# Adaptadores_Seriales.net
KiCad netlist of a schematic drawn in EAGLE
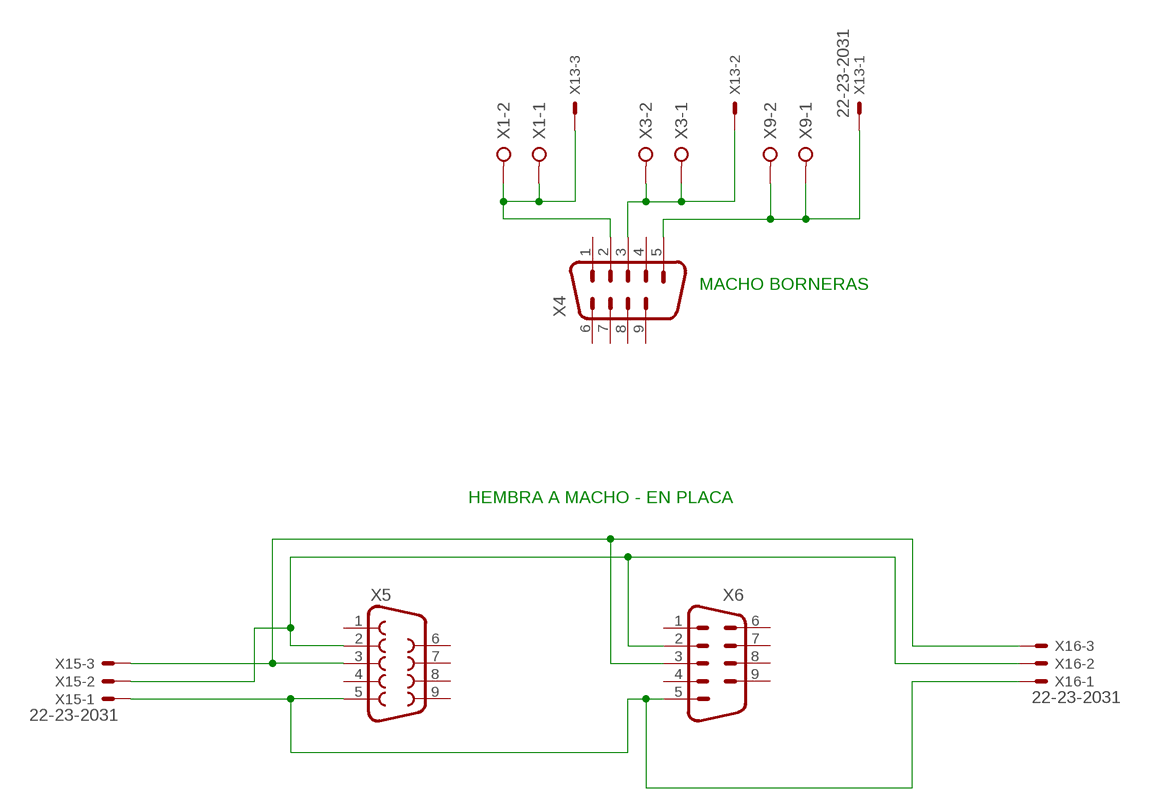
[diagram p0: schematic, sheet 1, part 1 of 2]
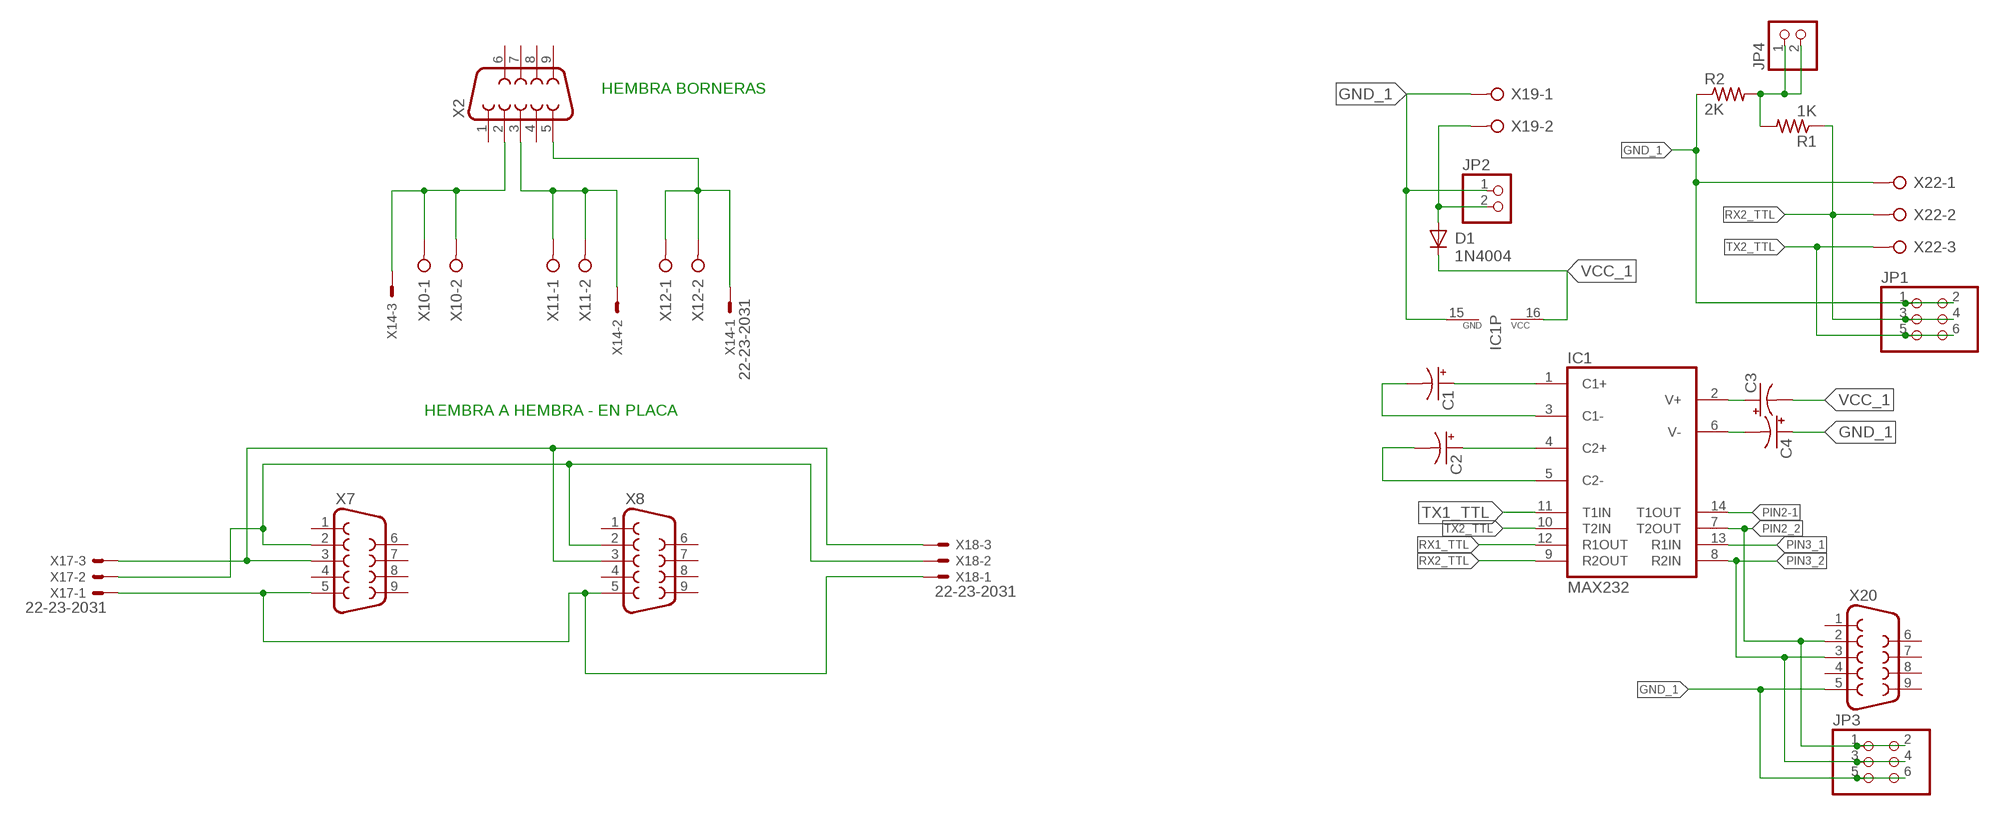
[diagram p1: schematic, sheet 1, part 2 of 2]

(export (version "E")
  (design (tool "Eeschema 10.0.6"))
  (components
    (comp (ref "C1")
      (value "10UF-25V-20%(PTH)KIT")
      (footprint "eagle-import:CPOL-RADIAL-10UF-25V-KIT")
      (libsource (lib "eagle-import") (part "10UF-25V-20%(PTH)KIT"))
    )
    (comp (ref "C2")
      (value "10UF-25V-20%(PTH)KIT")
      (footprint "eagle-import:CPOL-RADIAL-10UF-25V-KIT")
      (libsource (lib "eagle-import") (part "10UF-25V-20%(PTH)KIT"))
    )
    (comp (ref "C3")
      (value "10UF-25V-20%(PTH)KIT")
      (footprint "eagle-import:CPOL-RADIAL-10UF-25V-KIT")
      (libsource (lib "eagle-import") (part "10UF-25V-20%(PTH)KIT"))
    )
    (comp (ref "C4")
      (value "10UF-25V-20%(PTH)KIT")
      (footprint "eagle-import:CPOL-RADIAL-10UF-25V-KIT")
      (libsource (lib "eagle-import") (part "10UF-25V-20%(PTH)KIT"))
    )
    (comp (ref "D1")
      (value "1N4004")
      (footprint "eagle-import:DO41-10")
      (libsource (lib "eagle-import") (part "1N4004"))
    )
    (comp (ref "IC1")
      (value "MAX232")
      (footprint "eagle-import:DIL16")
      (fields (field (name "MF") "MAXIM") (field (name "MPN") "MAX232ACPE+"))
      (libsource (lib "eagle-import") (part "MAX232"))
    )
    (comp (ref "JP1")
      (value "PINHD-2X3")
      (footprint "eagle-import:2X03")
      (libsource (lib "eagle-import") (part "PINHD-2X3"))
    )
    (comp (ref "JP2")
      (value "PINHD-1X2")
      (footprint "eagle-import:1X02")
      (libsource (lib "eagle-import") (part "PINHD-1X2"))
    )
    (comp (ref "JP3")
      (value "PINHD-2X3")
      (footprint "eagle-import:2X03")
      (libsource (lib "eagle-import") (part "PINHD-2X3"))
    )
    (comp (ref "JP4")
      (value "PINHD-1X2")
      (footprint "eagle-import:1X02")
      (libsource (lib "eagle-import") (part "PINHD-1X2"))
    )
    (comp (ref "R1")
      (value "1K")
      (footprint "eagle-import:0204V")
      (libsource (lib "eagle-import") (part "R-US_0204/2V"))
    )
    (comp (ref "R2")
      (value "2K")
      (footprint "eagle-import:0204V")
      (libsource (lib "eagle-import") (part "R-US_0204/2V"))
    )
    (comp (ref "X1")
      (value "W237-02P")
      (footprint "eagle-import:W237-132")
      (libsource (lib "eagle-import") (part "W237-02P"))
    )
    (comp (ref "X2")
      (value "F09HP")
      (footprint "eagle-import:F09HP")
      (libsource (lib "eagle-import") (part "F09HP"))
    )
    (comp (ref "X3")
      (value "W237-02P")
      (footprint "eagle-import:W237-132")
      (libsource (lib "eagle-import") (part "W237-02P"))
    )
    (comp (ref "X4")
      (value "M09HP")
      (footprint "eagle-import:M09HP")
      (libsource (lib "eagle-import") (part "M09HP"))
    )
    (comp (ref "X5")
      (value "F09D")
      (footprint "eagle-import:F09D")
      (libsource (lib "eagle-import") (part "F09D"))
    )
    (comp (ref "X6")
      (value "M09D")
      (footprint "eagle-import:M09D")
      (libsource (lib "eagle-import") (part "M09D"))
    )
    (comp (ref "X7")
      (value "F09D")
      (footprint "eagle-import:F09D")
      (libsource (lib "eagle-import") (part "F09D"))
    )
    (comp (ref "X8")
      (value "F09D")
      (footprint "eagle-import:F09D")
      (libsource (lib "eagle-import") (part "F09D"))
    )
    (comp (ref "X9")
      (value "W237-02P")
      (footprint "eagle-import:W237-132")
      (libsource (lib "eagle-import") (part "W237-02P"))
    )
    (comp (ref "X10")
      (value "W237-02P")
      (footprint "eagle-import:W237-132")
      (libsource (lib "eagle-import") (part "W237-02P"))
    )
    (comp (ref "X11")
      (value "W237-02P")
      (footprint "eagle-import:W237-132")
      (libsource (lib "eagle-import") (part "W237-02P"))
    )
    (comp (ref "X12")
      (value "W237-02P")
      (footprint "eagle-import:W237-132")
      (libsource (lib "eagle-import") (part "W237-02P"))
    )
    (comp (ref "X13")
      (value "22-23-2031")
      (footprint "eagle-import:22-23-2031")
      (fields (field (name "MF") "MOLEX"))
      (libsource (lib "eagle-import") (part "22-23-2031"))
    )
    (comp (ref "X14")
      (value "22-23-2031")
      (footprint "eagle-import:22-23-2031")
      (fields (field (name "MF") "MOLEX"))
      (libsource (lib "eagle-import") (part "22-23-2031"))
    )
    (comp (ref "X15")
      (value "22-23-2031")
      (footprint "eagle-import:22-23-2031")
      (fields (field (name "MF") "MOLEX"))
      (libsource (lib "eagle-import") (part "22-23-2031"))
    )
    (comp (ref "X16")
      (value "22-23-2031")
      (footprint "eagle-import:22-23-2031")
      (fields (field (name "MF") "MOLEX"))
      (libsource (lib "eagle-import") (part "22-23-2031"))
    )
    (comp (ref "X17")
      (value "22-23-2031")
      (footprint "eagle-import:22-23-2031")
      (fields (field (name "MF") "MOLEX"))
      (libsource (lib "eagle-import") (part "22-23-2031"))
    )
    (comp (ref "X18")
      (value "22-23-2031")
      (footprint "eagle-import:22-23-2031")
      (fields (field (name "MF") "MOLEX"))
      (libsource (lib "eagle-import") (part "22-23-2031"))
    )
    (comp (ref "X19")
      (value "W237-02P")
      (footprint "eagle-import:W237-132")
      (fields (field (name "OC_FARNELL") "unknown") (field (name "OC_NEWARK") "unknown"))
      (libsource (lib "eagle-import") (part "W237-02P"))
    )
    (comp (ref "X20")
      (value "F09D")
      (footprint "eagle-import:F09D")
      (fields (field (name "OC_FARNELL") "unknown") (field (name "OC_NEWARK") "unknown"))
      (libsource (lib "eagle-import") (part "F09D"))
    )
    (comp (ref "X22")
      (value "W237-03P")
      (footprint "eagle-import:W237-133")
      (libsource (lib "eagle-import") (part "W237-03P"))
    )
  )
  (nets
    (net (code "1") (name "GND_1") (class "Default")
      (node (ref "C4") (pin "1") (pinfunction "+_1") (pintype "passive"))
      (node (ref "IC1") (pin "15") (pinfunction "GND_15") (pintype "power_in"))
      (node (ref "JP1") (pin "1") (pinfunction "1_1") (pintype "passive"))
      (node (ref "JP1") (pin "2") (pinfunction "2_2") (pintype "passive"))
      (node (ref "JP2") (pin "1") (pinfunction "1_1") (pintype "passive"))
      (node (ref "JP3") (pin "5") (pinfunction "5_5") (pintype "passive"))
      (node (ref "JP3") (pin "6") (pinfunction "6_6") (pintype "passive"))
      (node (ref "R2") (pin "1") (pinfunction "1_1") (pintype "passive"))
      (node (ref "X19") (pin "1") (pinfunction "KL_1") (pintype "passive"))
      (node (ref "X20") (pin "5") (pinfunction "5_5") (pintype "passive"))
      (node (ref "X22") (pin "1") (pinfunction "KL_1") (pintype "passive"))
    )
    (net (code "2") (name "Net-(C1-+)") (class "Default")
      (node (ref "C1") (pin "1") (pinfunction "+_1") (pintype "passive"))
      (node (ref "IC1") (pin "1") (pinfunction "C1+_1") (pintype "bidirectional"))
    )
    (net (code "3") (name "Net-(C1--)") (class "Default")
      (node (ref "C1") (pin "2") (pinfunction "-_2") (pintype "passive"))
      (node (ref "IC1") (pin "3") (pinfunction "C1-_3") (pintype "bidirectional"))
    )
    (net (code "4") (name "Net-(C2-+)") (class "Default")
      (node (ref "C2") (pin "1") (pinfunction "+_1") (pintype "passive"))
      (node (ref "IC1") (pin "4") (pinfunction "C2+_4") (pintype "bidirectional"))
    )
    (net (code "5") (name "Net-(C2--)") (class "Default")
      (node (ref "C2") (pin "2") (pinfunction "-_2") (pintype "passive"))
      (node (ref "IC1") (pin "5") (pinfunction "C2-_5") (pintype "bidirectional"))
    )
    (net (code "6") (name "Net-(C3-+)") (class "Default")
      (node (ref "C3") (pin "1") (pinfunction "+_1") (pintype "passive"))
      (node (ref "IC1") (pin "2") (pinfunction "V+_2") (pintype "bidirectional"))
    )
    (net (code "7") (name "Net-(C4--)") (class "Default")
      (node (ref "C4") (pin "2") (pinfunction "-_2") (pintype "passive"))
      (node (ref "IC1") (pin "6") (pinfunction "V-_6") (pintype "bidirectional"))
    )
    (net (code "8") (name "Net-(JP4-Pad1)") (class "Default")
      (node (ref "JP4") (pin "1") (pinfunction "1_1") (pintype "passive"))
      (node (ref "JP4") (pin "2") (pinfunction "2_2") (pintype "passive"))
      (node (ref "R1") (pin "2") (pinfunction "2_2") (pintype "passive"))
      (node (ref "R2") (pin "2") (pinfunction "2_2") (pintype "passive"))
    )
    (net (code "9") (name "Net-(X10A-KL)") (class "Default")
      (node (ref "X10") (pin "1") (pinfunction "KL_1") (pintype "passive"))
      (node (ref "X10") (pin "2") (pinfunction "KL_2") (pintype "passive"))
      (node (ref "X14") (pin "3") (pinfunction "S_3") (pintype "passive"))
      (node (ref "X2") (pin "2") (pinfunction "2_2") (pintype "passive"))
    )
    (net (code "10") (name "Net-(X11A-KL)") (class "Default")
      (node (ref "X11") (pin "1") (pinfunction "KL_1") (pintype "passive"))
      (node (ref "X11") (pin "2") (pinfunction "KL_2") (pintype "passive"))
      (node (ref "X14") (pin "2") (pinfunction "S_2") (pintype "passive"))
      (node (ref "X2") (pin "3") (pinfunction "3_3") (pintype "passive"))
    )
    (net (code "11") (name "Net-(X12A-KL)") (class "Default")
      (node (ref "X12") (pin "1") (pinfunction "KL_1") (pintype "passive"))
      (node (ref "X12") (pin "2") (pinfunction "KL_2") (pintype "passive"))
      (node (ref "X14") (pin "1") (pinfunction "S_1") (pintype "passive"))
      (node (ref "X2") (pin "5") (pinfunction "5_5") (pintype "passive"))
    )
    (net (code "12") (name "Net-(X13A-S)") (class "Default")
      (node (ref "X13") (pin "1") (pinfunction "S_1") (pintype "passive"))
      (node (ref "X4") (pin "5") (pinfunction "5_5") (pintype "passive"))
      (node (ref "X9") (pin "1") (pinfunction "KL_1") (pintype "passive"))
      (node (ref "X9") (pin "2") (pinfunction "KL_2") (pintype "passive"))
    )
    (net (code "13") (name "Net-(X13B-S)") (class "Default")
      (node (ref "X13") (pin "2") (pinfunction "S_2") (pintype "passive"))
      (node (ref "X3") (pin "1") (pinfunction "KL_1") (pintype "passive"))
      (node (ref "X3") (pin "2") (pinfunction "KL_2") (pintype "passive"))
      (node (ref "X4") (pin "3") (pinfunction "3_3") (pintype "passive"))
    )
    (net (code "14") (name "Net-(X13C-S)") (class "Default")
      (node (ref "X1") (pin "1") (pinfunction "KL_1") (pintype "passive"))
      (node (ref "X1") (pin "2") (pinfunction "KL_2") (pintype "passive"))
      (node (ref "X13") (pin "3") (pinfunction "S_3") (pintype "passive"))
      (node (ref "X4") (pin "2") (pinfunction "2_2") (pintype "passive"))
    )
    (net (code "15") (name "Net-(X15A-S)") (class "Default")
      (node (ref "X15") (pin "1") (pinfunction "S_1") (pintype "passive"))
      (node (ref "X16") (pin "1") (pinfunction "S_1") (pintype "passive"))
      (node (ref "X5") (pin "5") (pinfunction "5_5") (pintype "passive"))
      (node (ref "X6") (pin "5") (pinfunction "5_5") (pintype "passive"))
    )
    (net (code "16") (name "Net-(X15B-S)") (class "Default")
      (node (ref "X15") (pin "2") (pinfunction "S_2") (pintype "passive"))
      (node (ref "X16") (pin "2") (pinfunction "S_2") (pintype "passive"))
      (node (ref "X5") (pin "2") (pinfunction "2_2") (pintype "passive"))
      (node (ref "X6") (pin "2") (pinfunction "2_2") (pintype "passive"))
    )
    (net (code "17") (name "Net-(X15C-S)") (class "Default")
      (node (ref "X15") (pin "3") (pinfunction "S_3") (pintype "passive"))
      (node (ref "X16") (pin "3") (pinfunction "S_3") (pintype "passive"))
      (node (ref "X5") (pin "3") (pinfunction "3_3") (pintype "passive"))
      (node (ref "X6") (pin "3") (pinfunction "3_3") (pintype "passive"))
    )
    (net (code "18") (name "Net-(X17A-S)") (class "Default")
      (node (ref "X17") (pin "1") (pinfunction "S_1") (pintype "passive"))
      (node (ref "X18") (pin "1") (pinfunction "S_1") (pintype "passive"))
      (node (ref "X7") (pin "5") (pinfunction "5_5") (pintype "passive"))
      (node (ref "X8") (pin "5") (pinfunction "5_5") (pintype "passive"))
    )
    (net (code "19") (name "Net-(X17B-S)") (class "Default")
      (node (ref "X17") (pin "2") (pinfunction "S_2") (pintype "passive"))
      (node (ref "X18") (pin "2") (pinfunction "S_2") (pintype "passive"))
      (node (ref "X7") (pin "2") (pinfunction "2_2") (pintype "passive"))
      (node (ref "X8") (pin "2") (pinfunction "2_2") (pintype "passive"))
    )
    (net (code "20") (name "Net-(X17C-S)") (class "Default")
      (node (ref "X17") (pin "3") (pinfunction "S_3") (pintype "passive"))
      (node (ref "X18") (pin "3") (pinfunction "S_3") (pintype "passive"))
      (node (ref "X7") (pin "3") (pinfunction "3_3") (pintype "passive"))
      (node (ref "X8") (pin "3") (pinfunction "3_3") (pintype "passive"))
    )
    (net (code "21") (name "Net-(X19B-KL)") (class "Default")
      (node (ref "D1") (pin "A") (pinfunction "A_A") (pintype "passive"))
      (node (ref "JP2") (pin "2") (pinfunction "2_2") (pintype "passive"))
      (node (ref "X19") (pin "2") (pinfunction "KL_2") (pintype "passive"))
    )
    (net (code "22") (name "PIN2-1") (class "Default")
      (node (ref "IC1") (pin "14") (pinfunction "T1OUT_14") (pintype "output"))
    )
    (net (code "23") (name "PIN2_2") (class "Default")
      (node (ref "IC1") (pin "7") (pinfunction "T2OUT_7") (pintype "output"))
      (node (ref "JP3") (pin "1") (pinfunction "1_1") (pintype "passive"))
      (node (ref "JP3") (pin "2") (pinfunction "2_2") (pintype "passive"))
      (node (ref "X20") (pin "2") (pinfunction "2_2") (pintype "passive"))
    )
    (net (code "24") (name "PIN3_1") (class "Default")
      (node (ref "IC1") (pin "13") (pinfunction "R1IN_13") (pintype "input"))
    )
    (net (code "25") (name "PIN3_2") (class "Default")
      (node (ref "IC1") (pin "8") (pinfunction "R2IN_8") (pintype "input"))
      (node (ref "JP3") (pin "3") (pinfunction "3_3") (pintype "passive"))
      (node (ref "JP3") (pin "4") (pinfunction "4_4") (pintype "passive"))
      (node (ref "X20") (pin "3") (pinfunction "3_3") (pintype "passive"))
    )
    (net (code "26") (name "RX1_TTL") (class "Default")
      (node (ref "IC1") (pin "12") (pinfunction "R1OUT_12") (pintype "output"))
    )
    (net (code "27") (name "RX2_TTL") (class "Default")
      (node (ref "IC1") (pin "9") (pinfunction "R2OUT_9") (pintype "output"))
      (node (ref "JP1") (pin "3") (pinfunction "3_3") (pintype "passive"))
      (node (ref "JP1") (pin "4") (pinfunction "4_4") (pintype "passive"))
      (node (ref "R1") (pin "1") (pinfunction "1_1") (pintype "passive"))
      (node (ref "X22") (pin "2") (pinfunction "KL_2") (pintype "passive"))
    )
    (net (code "28") (name "TX1_TTL") (class "Default")
      (node (ref "IC1") (pin "11") (pinfunction "T1IN_11") (pintype "input"))
    )
    (net (code "29") (name "TX2_TTL") (class "Default")
      (node (ref "IC1") (pin "10") (pinfunction "T2IN_10") (pintype "input"))
      (node (ref "JP1") (pin "5") (pinfunction "5_5") (pintype "passive"))
      (node (ref "JP1") (pin "6") (pinfunction "6_6") (pintype "passive"))
      (node (ref "X22") (pin "3") (pinfunction "KL_3") (pintype "passive"))
    )
    (net (code "30") (name "VCC_1") (class "Default")
      (node (ref "C3") (pin "2") (pinfunction "-_2") (pintype "passive"))
      (node (ref "D1") (pin "C") (pinfunction "C_C") (pintype "passive"))
      (node (ref "IC1") (pin "16") (pinfunction "VCC_16") (pintype "power_in"))
    )
    (net (code "31") (name "unconnected-(X2-Pad1)") (class "Default")
      (node (ref "X2") (pin "1") (pinfunction "1_1") (pintype "passive"))
    )
    (net (code "32") (name "unconnected-(X2-Pad4)") (class "Default")
      (node (ref "X2") (pin "4") (pinfunction "4_4") (pintype "passive"))
    )
    (net (code "33") (name "unconnected-(X2-Pad6)") (class "Default")
      (node (ref "X2") (pin "6") (pinfunction "6_6") (pintype "passive"))
    )
    (net (code "34") (name "unconnected-(X2-Pad7)") (class "Default")
      (node (ref "X2") (pin "7") (pinfunction "7_7") (pintype "passive"))
    )
    (net (code "35") (name "unconnected-(X2-Pad8)") (class "Default")
      (node (ref "X2") (pin "8") (pinfunction "8_8") (pintype "passive"))
    )
    (net (code "36") (name "unconnected-(X2-Pad9)") (class "Default")
      (node (ref "X2") (pin "9") (pinfunction "9_9") (pintype "passive"))
    )
    (net (code "37") (name "unconnected-(X4-Pad1)") (class "Default")
      (node (ref "X4") (pin "1") (pinfunction "1_1") (pintype "passive"))
    )
    (net (code "38") (name "unconnected-(X4-Pad4)") (class "Default")
      (node (ref "X4") (pin "4") (pinfunction "4_4") (pintype "passive"))
    )
    (net (code "39") (name "unconnected-(X4-Pad6)") (class "Default")
      (node (ref "X4") (pin "6") (pinfunction "6_6") (pintype "passive"))
    )
    (net (code "40") (name "unconnected-(X4-Pad7)") (class "Default")
      (node (ref "X4") (pin "7") (pinfunction "7_7") (pintype "passive"))
    )
    (net (code "41") (name "unconnected-(X4-Pad8)") (class "Default")
      (node (ref "X4") (pin "8") (pinfunction "8_8") (pintype "passive"))
    )
    (net (code "42") (name "unconnected-(X4-Pad9)") (class "Default")
      (node (ref "X4") (pin "9") (pinfunction "9_9") (pintype "passive"))
    )
    (net (code "43") (name "unconnected-(X5-Pad1)") (class "Default")
      (node (ref "X5") (pin "1") (pinfunction "1_1") (pintype "passive"))
    )
    (net (code "44") (name "unconnected-(X5-Pad4)") (class "Default")
      (node (ref "X5") (pin "4") (pinfunction "4_4") (pintype "passive"))
    )
    (net (code "45") (name "unconnected-(X5-Pad6)") (class "Default")
      (node (ref "X5") (pin "6") (pinfunction "6_6") (pintype "passive"))
    )
    (net (code "46") (name "unconnected-(X5-Pad7)") (class "Default")
      (node (ref "X5") (pin "7") (pinfunction "7_7") (pintype "passive"))
    )
    (net (code "47") (name "unconnected-(X5-Pad8)") (class "Default")
      (node (ref "X5") (pin "8") (pinfunction "8_8") (pintype "passive"))
    )
    (net (code "48") (name "unconnected-(X5-Pad9)") (class "Default")
      (node (ref "X5") (pin "9") (pinfunction "9_9") (pintype "passive"))
    )
    (net (code "49") (name "unconnected-(X6-Pad1)") (class "Default")
      (node (ref "X6") (pin "1") (pinfunction "1_1") (pintype "passive"))
    )
    (net (code "50") (name "unconnected-(X6-Pad4)") (class "Default")
      (node (ref "X6") (pin "4") (pinfunction "4_4") (pintype "passive"))
    )
    (net (code "51") (name "unconnected-(X6-Pad6)") (class "Default")
      (node (ref "X6") (pin "6") (pinfunction "6_6") (pintype "passive"))
    )
    (net (code "52") (name "unconnected-(X6-Pad7)") (class "Default")
      (node (ref "X6") (pin "7") (pinfunction "7_7") (pintype "passive"))
    )
    (net (code "53") (name "unconnected-(X6-Pad8)") (class "Default")
      (node (ref "X6") (pin "8") (pinfunction "8_8") (pintype "passive"))
    )
    (net (code "54") (name "unconnected-(X6-Pad9)") (class "Default")
      (node (ref "X6") (pin "9") (pinfunction "9_9") (pintype "passive"))
    )
    (net (code "55") (name "unconnected-(X7-Pad1)") (class "Default")
      (node (ref "X7") (pin "1") (pinfunction "1_1") (pintype "passive"))
    )
    (net (code "56") (name "unconnected-(X7-Pad4)") (class "Default")
      (node (ref "X7") (pin "4") (pinfunction "4_4") (pintype "passive"))
    )
    (net (code "57") (name "unconnected-(X7-Pad6)") (class "Default")
      (node (ref "X7") (pin "6") (pinfunction "6_6") (pintype "passive"))
    )
    (net (code "58") (name "unconnected-(X7-Pad7)") (class "Default")
      (node (ref "X7") (pin "7") (pinfunction "7_7") (pintype "passive"))
    )
    (net (code "59") (name "unconnected-(X7-Pad8)") (class "Default")
      (node (ref "X7") (pin "8") (pinfunction "8_8") (pintype "passive"))
    )
    (net (code "60") (name "unconnected-(X7-Pad9)") (class "Default")
      (node (ref "X7") (pin "9") (pinfunction "9_9") (pintype "passive"))
    )
    (net (code "61") (name "unconnected-(X8-Pad1)") (class "Default")
      (node (ref "X8") (pin "1") (pinfunction "1_1") (pintype "passive"))
    )
    (net (code "62") (name "unconnected-(X8-Pad4)") (class "Default")
      (node (ref "X8") (pin "4") (pinfunction "4_4") (pintype "passive"))
    )
    (net (code "63") (name "unconnected-(X8-Pad6)") (class "Default")
      (node (ref "X8") (pin "6") (pinfunction "6_6") (pintype "passive"))
    )
    (net (code "64") (name "unconnected-(X8-Pad7)") (class "Default")
      (node (ref "X8") (pin "7") (pinfunction "7_7") (pintype "passive"))
    )
    (net (code "65") (name "unconnected-(X8-Pad8)") (class "Default")
      (node (ref "X8") (pin "8") (pinfunction "8_8") (pintype "passive"))
    )
    (net (code "66") (name "unconnected-(X8-Pad9)") (class "Default")
      (node (ref "X8") (pin "9") (pinfunction "9_9") (pintype "passive"))
    )
    (net (code "67") (name "unconnected-(X20-Pad1)") (class "Default")
      (node (ref "X20") (pin "1") (pinfunction "1_1") (pintype "passive"))
    )
    (net (code "68") (name "unconnected-(X20-Pad4)") (class "Default")
      (node (ref "X20") (pin "4") (pinfunction "4_4") (pintype "passive"))
    )
    (net (code "69") (name "unconnected-(X20-Pad6)") (class "Default")
      (node (ref "X20") (pin "6") (pinfunction "6_6") (pintype "passive"))
    )
    (net (code "70") (name "unconnected-(X20-Pad7)") (class "Default")
      (node (ref "X20") (pin "7") (pinfunction "7_7") (pintype "passive"))
    )
    (net (code "71") (name "unconnected-(X20-Pad8)") (class "Default")
      (node (ref "X20") (pin "8") (pinfunction "8_8") (pintype "passive"))
    )
    (net (code "72") (name "unconnected-(X20-Pad9)") (class "Default")
      (node (ref "X20") (pin "9") (pinfunction "9_9") (pintype "passive"))
    )
  )
)
